# relay.net
KiCad netlist of a schematic drawn in EAGLE
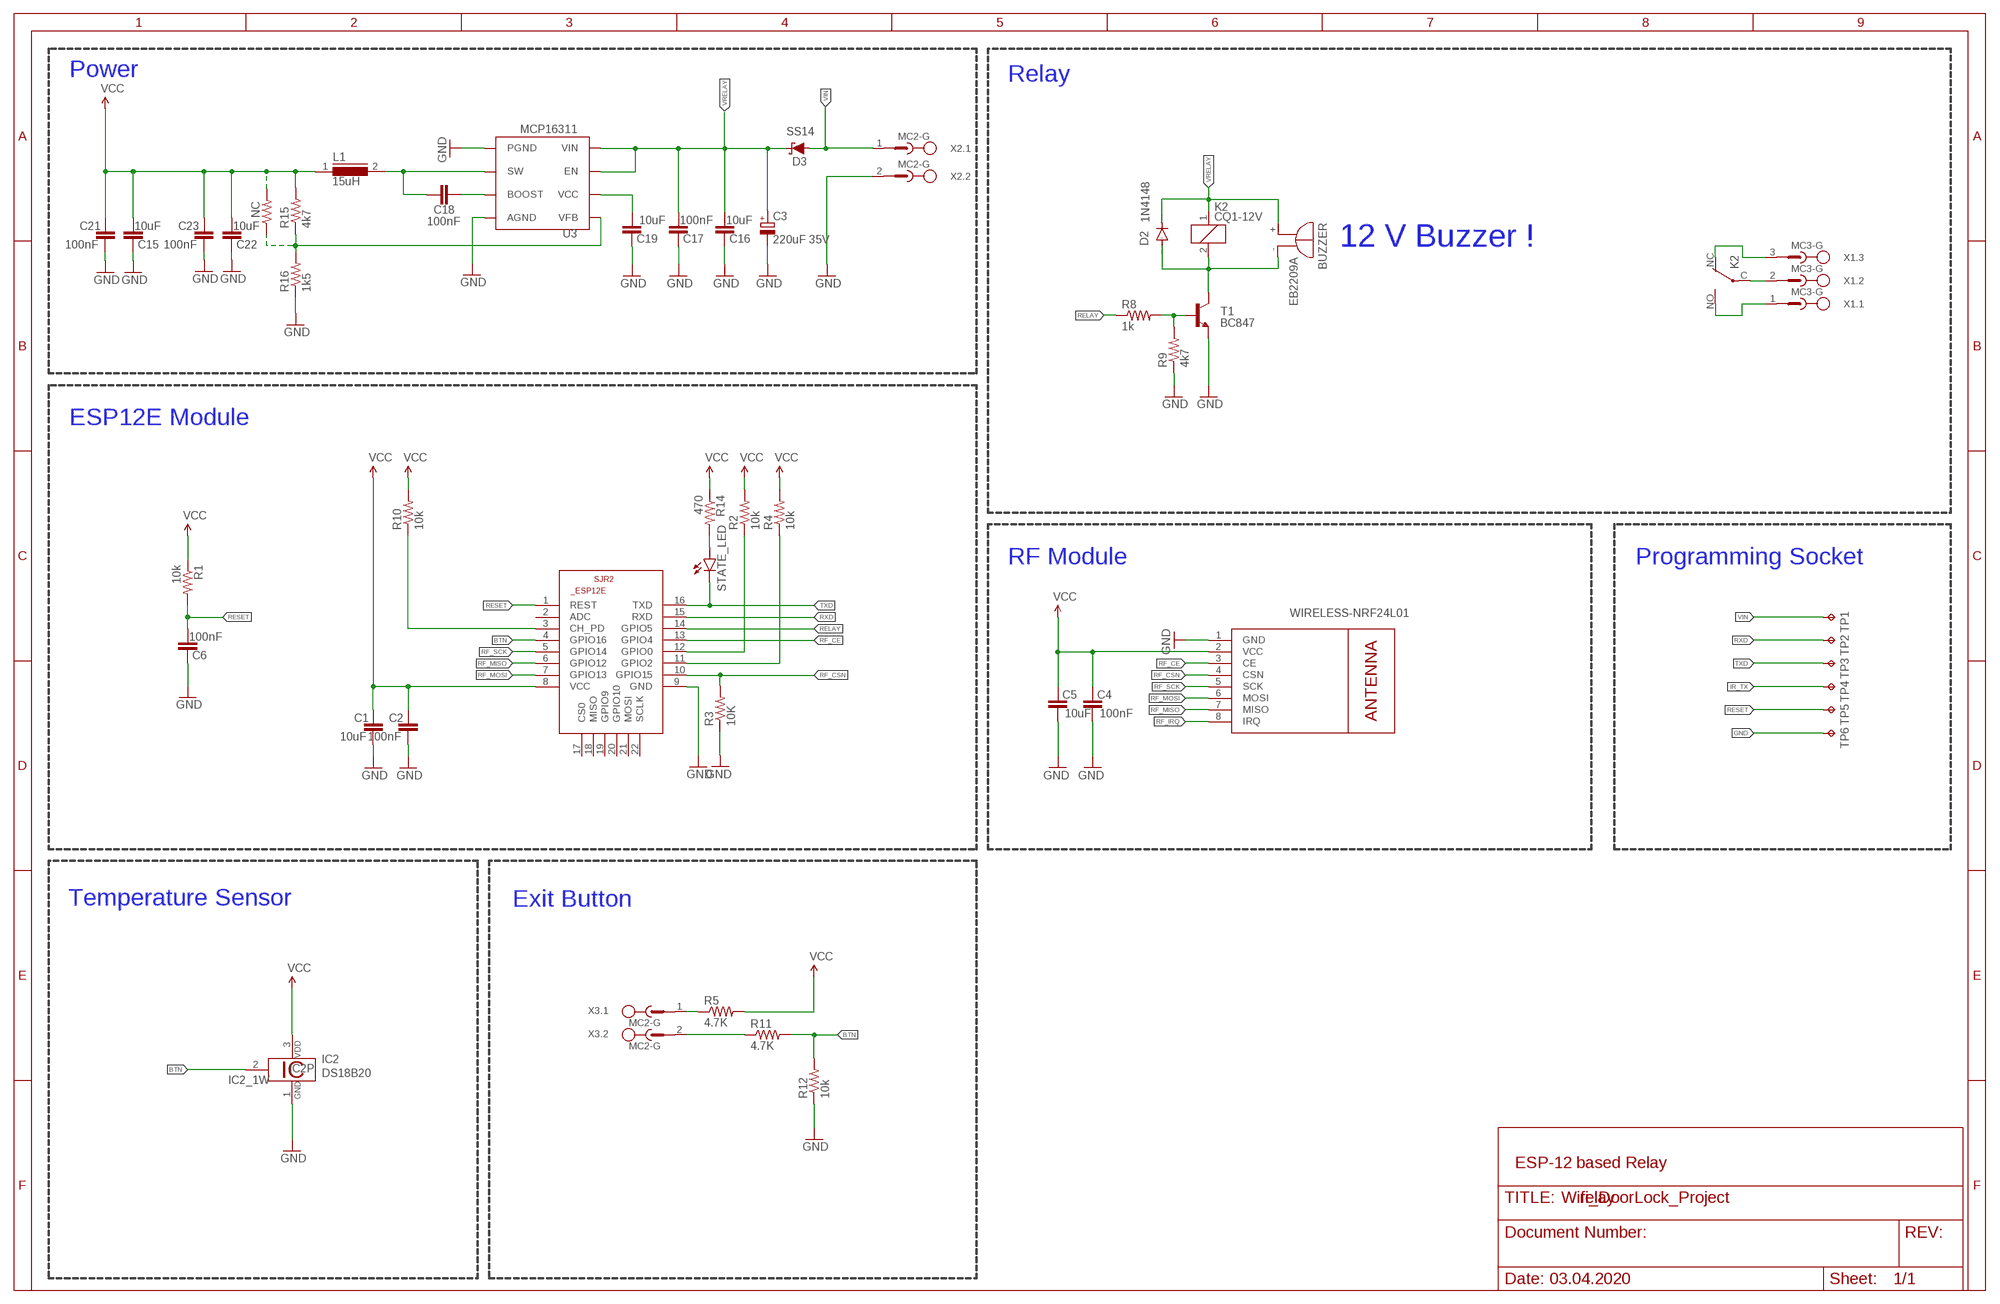
[diagram p0: schematic, sheet 1]

(export (version "E")
  (design (tool "Eeschema 10.0.6"))
  (components
    (comp (ref "BUZZER")
      (value "EB2209A")
      (footprint "eagle-import:EB2209A")
      (libsource (lib "eagle-import") (part "EB2209A"))
    )
    (comp (ref "C1")
      (value "10uF")
      (footprint "eagle-import:C0805")
      (libsource (lib "eagle-import") (part "C-EUC0805"))
    )
    (comp (ref "C2")
      (value "100nF")
      (footprint "eagle-import:C0805")
      (libsource (lib "eagle-import") (part "C-EUC0805"))
    )
    (comp (ref "C3")
      (value "220uF 35V")
      (footprint "eagle-import:150CLZ-0810")
      (libsource (lib "eagle-import") (part "CPOL-EU150CLZ-0810"))
    )
    (comp (ref "C4")
      (value "100nF")
      (footprint "eagle-import:C0805")
      (libsource (lib "eagle-import") (part "C-EUC0805"))
    )
    (comp (ref "C5")
      (value "10uF")
      (footprint "eagle-import:C0805")
      (libsource (lib "eagle-import") (part "C-EUC0805"))
    )
    (comp (ref "C6")
      (value "100nF")
      (footprint "eagle-import:C0805")
      (libsource (lib "eagle-import") (part "C-EUC0805"))
    )
    (comp (ref "C15")
      (value "10uF")
      (footprint "eagle-import:C0805")
      (libsource (lib "eagle-import") (part "C-EUC0805"))
    )
    (comp (ref "C16")
      (value "10uF")
      (footprint "eagle-import:C0805")
      (libsource (lib "eagle-import") (part "C-EUC0805"))
    )
    (comp (ref "C17")
      (value "100nF")
      (footprint "eagle-import:C0805")
      (libsource (lib "eagle-import") (part "C-EUC0805"))
    )
    (comp (ref "C18")
      (value "100nF")
      (footprint "eagle-import:C0805")
      (libsource (lib "eagle-import") (part "C-EUC0805"))
    )
    (comp (ref "C19")
      (value "10uF")
      (footprint "eagle-import:C0805")
      (libsource (lib "eagle-import") (part "C-EUC0805"))
    )
    (comp (ref "C21")
      (value "100nF")
      (footprint "eagle-import:C0805")
      (libsource (lib "eagle-import") (part "C-EUC0805"))
    )
    (comp (ref "C22")
      (value "10uF")
      (footprint "eagle-import:C0805")
      (libsource (lib "eagle-import") (part "C-EUC0805"))
    )
    (comp (ref "C23")
      (value "100nF")
      (footprint "eagle-import:C0805")
      (libsource (lib "eagle-import") (part "C-EUC0805"))
    )
    (comp (ref "D2")
      (value "1N4148")
      (footprint "eagle-import:DO-214AC")
      (libsource (lib "eagle-import") (part "DIODE-DO-214AC"))
    )
    (comp (ref "D3")
      (value "SS14")
      (footprint "eagle-import:SMA-DIODE")
      (libsource (lib "eagle-import") (part "DIODE-SCHOTTKY-SS14"))
    )
    (comp (ref "IC2")
      (value "DS18B20")
      (footprint "eagle-import:TO92-")
      (libsource (lib "eagle-import") (part "DS18B20"))
    )
    (comp (ref "K2")
      (value "CQ1-12V")
      (footprint "eagle-import:CQ1")
      (libsource (lib "eagle-import") (part "CQ1-12V"))
    )
    (comp (ref "L1")
      (value "15uH")
      (footprint "eagle-import:DR74")
      (libsource (lib "eagle-import") (part "DR74"))
    )
    (comp (ref "M1")
      (value "WIRELESS-NRF24L01")
      (footprint "eagle-import:WIRELESS-NRF24L01")
      (libsource (lib "eagle-import") (part "WIRELESS-NRF24L01"))
    )
    (comp (ref "NC")
      (value "R-US_M0805")
      (footprint "eagle-import:M0805")
      (libsource (lib "eagle-import") (part "R-US_M0805"))
    )
    (comp (ref "R1")
      (value "10k")
      (footprint "eagle-import:M0805")
      (libsource (lib "eagle-import") (part "R-US_M0805"))
    )
    (comp (ref "R2")
      (value "10k")
      (footprint "eagle-import:M0805")
      (libsource (lib "eagle-import") (part "R-US_M0805"))
    )
    (comp (ref "R3")
      (value "10K")
      (footprint "eagle-import:M0805")
      (libsource (lib "eagle-import") (part "R-US_M0805"))
    )
    (comp (ref "R4")
      (value "10k")
      (footprint "eagle-import:M0805")
      (libsource (lib "eagle-import") (part "R-US_M0805"))
    )
    (comp (ref "R5")
      (value "4.7K")
      (footprint "eagle-import:M0805")
      (libsource (lib "eagle-import") (part "R-US_M0805"))
    )
    (comp (ref "R8")
      (value "1k")
      (footprint "eagle-import:M0805")
      (libsource (lib "eagle-import") (part "R-US_M0805"))
    )
    (comp (ref "R9")
      (value "4k7")
      (footprint "eagle-import:M0805")
      (libsource (lib "eagle-import") (part "R-US_M0805"))
    )
    (comp (ref "R10")
      (value "10k")
      (footprint "eagle-import:M0805")
      (libsource (lib "eagle-import") (part "R-US_M0805"))
    )
    (comp (ref "R11")
      (value "4.7K")
      (footprint "eagle-import:M0805")
      (libsource (lib "eagle-import") (part "R-US_M0805"))
    )
    (comp (ref "R12")
      (value "10k")
      (footprint "eagle-import:M0805")
      (libsource (lib "eagle-import") (part "R-US_M0805"))
    )
    (comp (ref "R14")
      (value "470")
      (footprint "eagle-import:M0805")
      (libsource (lib "eagle-import") (part "R-US_M0805"))
    )
    (comp (ref "R15")
      (value "4k7")
      (footprint "eagle-import:M0805")
      (libsource (lib "eagle-import") (part "R-US_M0805"))
    )
    (comp (ref "R16")
      (value "1k5")
      (footprint "eagle-import:M0805")
      (libsource (lib "eagle-import") (part "R-US_M0805"))
    )
    (comp (ref "SJR2")
      (value "ESP8266-12EESP12E")
      (footprint "eagle-import:ESP8266-ESP12E")
      (libsource (lib "eagle-import") (part "ESP8266-12EESP12E"))
    )
    (comp (ref "STATE_LED")
      (value "LED3MM")
      (footprint "eagle-import:LED3MM")
      (libsource (lib "eagle-import") (part "LED3MM"))
    )
    (comp (ref "T1")
      (value "BC847")
      (footprint "eagle-import:SOT23")
      (libsource (lib "eagle-import") (part "BC847"))
    )
    (comp (ref "TP1")
      (value "TPTP20SQ")
      (footprint "eagle-import:TP20SQ")
      (libsource (lib "eagle-import") (part "TPTP20SQ"))
    )
    (comp (ref "TP2")
      (value "TPTP20SQ")
      (footprint "eagle-import:TP20SQ")
      (libsource (lib "eagle-import") (part "TPTP20SQ"))
    )
    (comp (ref "TP3")
      (value "TPTP20SQ")
      (footprint "eagle-import:TP20SQ")
      (libsource (lib "eagle-import") (part "TPTP20SQ"))
    )
    (comp (ref "TP4")
      (value "TPTP20SQ")
      (footprint "eagle-import:TP20SQ")
      (libsource (lib "eagle-import") (part "TPTP20SQ"))
    )
    (comp (ref "TP5")
      (value "TPTP20SQ")
      (footprint "eagle-import:TP20SQ")
      (libsource (lib "eagle-import") (part "TPTP20SQ"))
    )
    (comp (ref "TP6")
      (value "TPTP20SQ")
      (footprint "eagle-import:TP20SQ")
      (libsource (lib "eagle-import") (part "TPTP20SQ"))
    )
    (comp (ref "U3")
      (value "MCP16311")
      (footprint "eagle-import:MSOP8")
      (libsource (lib "eagle-import") (part "MCP16311"))
    )
    (comp (ref "X1")
      (value "MC3-G")
      (footprint "eagle-import:MC3-G")
      (libsource (lib "eagle-import") (part "MC3-G"))
    )
    (comp (ref "X2")
      (value "MC2-G")
      (footprint "eagle-import:MC2-G")
      (libsource (lib "eagle-import") (part "MC2-G"))
    )
    (comp (ref "X3")
      (value "MC2-G")
      (footprint "eagle-import:MC2-G")
      (libsource (lib "eagle-import") (part "MC2-G"))
    )
  )
  (nets
    (net (code "1") (name "BTN") (class "Default")
      (node (ref "IC2") (pin "2") (pinfunction "1W_2") (pintype "power_in"))
      (node (ref "R11") (pin "2") (pinfunction "2_2") (pintype "passive"))
      (node (ref "R12") (pin "2") (pinfunction "2_2") (pintype "passive"))
      (node (ref "SJR2") (pin "4") (pinfunction "GPIO16_4") (pintype "bidirectional"))
    )
    (net (code "2") (name "GND") (class "Default")
      (node (ref "C1") (pin "2") (pinfunction "2_2") (pintype "passive"))
      (node (ref "C15") (pin "1") (pinfunction "1_1") (pintype "passive"))
      (node (ref "C16") (pin "1") (pinfunction "1_1") (pintype "passive"))
      (node (ref "C17") (pin "1") (pinfunction "1_1") (pintype "passive"))
      (node (ref "C19") (pin "1") (pinfunction "1_1") (pintype "passive"))
      (node (ref "C2") (pin "2") (pinfunction "2_2") (pintype "passive"))
      (node (ref "C21") (pin "2") (pinfunction "2_2") (pintype "passive"))
      (node (ref "C22") (pin "1") (pinfunction "1_1") (pintype "passive"))
      (node (ref "C23") (pin "2") (pinfunction "2_2") (pintype "passive"))
      (node (ref "C3") (pin "-") (pinfunction "-_-") (pintype "passive"))
      (node (ref "C4") (pin "2") (pinfunction "2_2") (pintype "passive"))
      (node (ref "C5") (pin "2") (pinfunction "2_2") (pintype "passive"))
      (node (ref "C6") (pin "1") (pinfunction "1_1") (pintype "passive"))
      (node (ref "IC2") (pin "1") (pinfunction "GND_1") (pintype "power_in"))
      (node (ref "M1") (pin "1") (pinfunction "GND_1") (pintype "power_in"))
      (node (ref "R12") (pin "1") (pinfunction "1_1") (pintype "passive"))
      (node (ref "R16") (pin "1") (pinfunction "1_1") (pintype "passive"))
      (node (ref "R3") (pin "1") (pinfunction "1_1") (pintype "passive"))
      (node (ref "R9") (pin "1") (pinfunction "1_1") (pintype "passive"))
      (node (ref "SJR2") (pin "9") (pinfunction "GND_9") (pintype "bidirectional"))
      (node (ref "T1") (pin "2") (pinfunction "E_2") (pintype "passive"))
      (node (ref "TP6") (pin "TP") (pinfunction "TP_TP") (pintype "input"))
      (node (ref "U3") (pin "AGND") (pinfunction "AGND_AGND") (pintype "bidirectional"))
      (node (ref "U3") (pin "PGND") (pinfunction "PGND_PGND") (pintype "bidirectional"))
      (node (ref "X2") (pin "2") (pinfunction "SK_2") (pintype "passive"))
    )
    (net (code "3") (name "IR_TX") (class "Default")
      (node (ref "TP4") (pin "TP") (pinfunction "TP_TP") (pintype "input"))
    )
    (net (code "4") (name "Net-(C18-Pad1)") (class "Default")
      (node (ref "C18") (pin "1") (pinfunction "1_1") (pintype "passive"))
      (node (ref "U3") (pin "BOOST") (pinfunction "BOOST_BOOST") (pintype "bidirectional"))
    )
    (net (code "5") (name "Net-(C18-Pad2)") (class "Default")
      (node (ref "C18") (pin "2") (pinfunction "2_2") (pintype "passive"))
      (node (ref "L1") (pin "2") (pinfunction "2_2") (pintype "passive"))
      (node (ref "U3") (pin "SW") (pinfunction "SW_SW") (pintype "bidirectional"))
    )
    (net (code "6") (name "Net-(C19-Pad2)") (class "Default")
      (node (ref "C19") (pin "2") (pinfunction "2_2") (pintype "passive"))
      (node (ref "U3") (pin "VCC") (pinfunction "VCC_VCC") (pintype "bidirectional"))
    )
    (net (code "7") (name "Net-(K2B-O)") (class "Default")
      (node (ref "K2") (pin "NC") (pinfunction "O_NC") (pintype "passive"))
      (node (ref "X1") (pin "3") (pinfunction "SK_3") (pintype "passive"))
    )
    (net (code "8") (name "Net-(K2B-P)") (class "Default")
      (node (ref "K2") (pin "C") (pinfunction "P_C") (pintype "passive"))
      (node (ref "X1") (pin "2") (pinfunction "SK_2") (pintype "passive"))
    )
    (net (code "9") (name "Net-(K2B-S)") (class "Default")
      (node (ref "K2") (pin "NO") (pinfunction "S_NO") (pintype "passive"))
      (node (ref "X1") (pin "1") (pinfunction "SK_1") (pintype "passive"))
    )
    (net (code "10") (name "Net-(NC-Pad1)") (class "Default")
      (node (ref "NC") (pin "1") (pinfunction "1_1") (pintype "passive"))
      (node (ref "R15") (pin "1") (pinfunction "1_1") (pintype "passive"))
      (node (ref "R16") (pin "2") (pinfunction "2_2") (pintype "passive"))
      (node (ref "U3") (pin "VFB") (pinfunction "VFB_VFB") (pintype "bidirectional"))
    )
    (net (code "11") (name "Net-(R14-Pad2)") (class "Default")
      (node (ref "R14") (pin "2") (pinfunction "2_2") (pintype "passive"))
      (node (ref "STATE_LED") (pin "A") (pinfunction "A_A") (pintype "passive"))
    )
    (net (code "12") (name "Net-(SJR2-CH_PD)") (class "Default")
      (node (ref "R10") (pin "1") (pinfunction "1_1") (pintype "passive"))
      (node (ref "SJR2") (pin "3") (pinfunction "CH_PD_3") (pintype "bidirectional"))
    )
    (net (code "13") (name "Net-(SJR2-GPIO0)") (class "Default")
      (node (ref "R2") (pin "1") (pinfunction "1_1") (pintype "passive"))
      (node (ref "SJR2") (pin "12") (pinfunction "GPIO0_12") (pintype "bidirectional"))
    )
    (net (code "14") (name "Net-(SJR2-GPIO2)") (class "Default")
      (node (ref "R4") (pin "1") (pinfunction "1_1") (pintype "passive"))
      (node (ref "SJR2") (pin "11") (pinfunction "GPIO2_11") (pintype "bidirectional"))
    )
    (net (code "15") (name "Net-(T1-B)") (class "Default")
      (node (ref "R8") (pin "2") (pinfunction "2_2") (pintype "passive"))
      (node (ref "R9") (pin "2") (pinfunction "2_2") (pintype "passive"))
      (node (ref "T1") (pin "1") (pinfunction "B_1") (pintype "passive"))
    )
    (net (code "16") (name "Net-(T1-C)") (class "Default")
      (node (ref "BUZZER") (pin "-") (pinfunction "-_-") (pintype "passive"))
      (node (ref "D2") (pin "A") (pinfunction "A_A") (pintype "passive"))
      (node (ref "K2") (pin "2") (pinfunction "2_2") (pintype "passive"))
      (node (ref "T1") (pin "3") (pinfunction "C_3") (pintype "passive"))
    )
    (net (code "17") (name "Net-(X3A-SK)") (class "Default")
      (node (ref "R5") (pin "1") (pinfunction "1_1") (pintype "passive"))
      (node (ref "X3") (pin "1") (pinfunction "SK_1") (pintype "passive"))
    )
    (net (code "18") (name "Net-(X3B-SK)") (class "Default")
      (node (ref "R11") (pin "1") (pinfunction "1_1") (pintype "passive"))
      (node (ref "X3") (pin "2") (pinfunction "SK_2") (pintype "passive"))
    )
    (net (code "19") (name "RELAY") (class "Default")
      (node (ref "R8") (pin "1") (pinfunction "1_1") (pintype "passive"))
      (node (ref "SJR2") (pin "14") (pinfunction "GPIO5_14") (pintype "bidirectional"))
    )
    (net (code "20") (name "RESET") (class "Default")
      (node (ref "C6") (pin "2") (pinfunction "2_2") (pintype "passive"))
      (node (ref "R1") (pin "2") (pinfunction "2_2") (pintype "passive"))
      (node (ref "SJR2") (pin "1") (pinfunction "REST_1") (pintype "bidirectional"))
      (node (ref "TP5") (pin "TP") (pinfunction "TP_TP") (pintype "input"))
    )
    (net (code "21") (name "RF_CE") (class "Default")
      (node (ref "M1") (pin "3") (pinfunction "CE_3") (pintype "bidirectional"))
      (node (ref "SJR2") (pin "13") (pinfunction "GPIO4_13") (pintype "bidirectional"))
    )
    (net (code "22") (name "RF_CSN") (class "Default")
      (node (ref "M1") (pin "4") (pinfunction "CSN_4") (pintype "bidirectional"))
      (node (ref "R3") (pin "2") (pinfunction "2_2") (pintype "passive"))
      (node (ref "SJR2") (pin "10") (pinfunction "GPIO15_10") (pintype "bidirectional"))
    )
    (net (code "23") (name "RF_IRQ") (class "Default")
      (node (ref "M1") (pin "8") (pinfunction "IRQ_8") (pintype "bidirectional"))
    )
    (net (code "24") (name "RF_MISO") (class "Default")
      (node (ref "M1") (pin "7") (pinfunction "MISO_7") (pintype "bidirectional"))
      (node (ref "SJR2") (pin "6") (pinfunction "GPIO12_6") (pintype "bidirectional"))
    )
    (net (code "25") (name "RF_MOSI") (class "Default")
      (node (ref "M1") (pin "6") (pinfunction "MOSI_6") (pintype "bidirectional"))
      (node (ref "SJR2") (pin "7") (pinfunction "GPIO13_7") (pintype "bidirectional"))
    )
    (net (code "26") (name "RF_SCK") (class "Default")
      (node (ref "M1") (pin "5") (pinfunction "SCK_5") (pintype "bidirectional"))
      (node (ref "SJR2") (pin "5") (pinfunction "GPIO14_5") (pintype "bidirectional"))
    )
    (net (code "27") (name "RXD") (class "Default")
      (node (ref "SJR2") (pin "15") (pinfunction "RXD_15") (pintype "bidirectional"))
      (node (ref "TP2") (pin "TP") (pinfunction "TP_TP") (pintype "input"))
    )
    (net (code "28") (name "TXD") (class "Default")
      (node (ref "SJR2") (pin "16") (pinfunction "TXD_16") (pintype "bidirectional"))
      (node (ref "STATE_LED") (pin "K") (pinfunction "C_K") (pintype "passive"))
      (node (ref "TP3") (pin "TP") (pinfunction "TP_TP") (pintype "input"))
    )
    (net (code "29") (name "VCC") (class "Default")
      (node (ref "C1") (pin "1") (pinfunction "1_1") (pintype "passive"))
      (node (ref "C15") (pin "2") (pinfunction "2_2") (pintype "passive"))
      (node (ref "C2") (pin "1") (pinfunction "1_1") (pintype "passive"))
      (node (ref "C21") (pin "1") (pinfunction "1_1") (pintype "passive"))
      (node (ref "C22") (pin "2") (pinfunction "2_2") (pintype "passive"))
      (node (ref "C23") (pin "1") (pinfunction "1_1") (pintype "passive"))
      (node (ref "C4") (pin "1") (pinfunction "1_1") (pintype "passive"))
      (node (ref "C5") (pin "1") (pinfunction "1_1") (pintype "passive"))
      (node (ref "IC2") (pin "3") (pinfunction "VDD_3") (pintype "power_in"))
      (node (ref "L1") (pin "1") (pinfunction "1_1") (pintype "passive"))
      (node (ref "M1") (pin "2") (pinfunction "VCC_2") (pintype "power_in"))
      (node (ref "NC") (pin "2") (pinfunction "2_2") (pintype "passive"))
      (node (ref "R1") (pin "1") (pinfunction "1_1") (pintype "passive"))
      (node (ref "R10") (pin "2") (pinfunction "2_2") (pintype "passive"))
      (node (ref "R14") (pin "1") (pinfunction "1_1") (pintype "passive"))
      (node (ref "R15") (pin "2") (pinfunction "2_2") (pintype "passive"))
      (node (ref "R2") (pin "2") (pinfunction "2_2") (pintype "passive"))
      (node (ref "R4") (pin "2") (pinfunction "2_2") (pintype "passive"))
      (node (ref "R5") (pin "2") (pinfunction "2_2") (pintype "passive"))
      (node (ref "SJR2") (pin "8") (pinfunction "VCC_8") (pintype "bidirectional"))
    )
    (net (code "30") (name "VIN") (class "Default")
      (node (ref "D3") (pin "A") (pinfunction "A_A") (pintype "passive"))
      (node (ref "TP1") (pin "TP") (pinfunction "TP_TP") (pintype "input"))
      (node (ref "X2") (pin "1") (pinfunction "SK_1") (pintype "passive"))
    )
    (net (code "31") (name "VRELAY") (class "Default")
      (node (ref "BUZZER") (pin "+") (pinfunction "+_+") (pintype "passive"))
      (node (ref "C16") (pin "2") (pinfunction "2_2") (pintype "passive"))
      (node (ref "C17") (pin "2") (pinfunction "2_2") (pintype "passive"))
      (node (ref "C3") (pin "+") (pinfunction "+_+") (pintype "passive"))
      (node (ref "D2") (pin "C") (pinfunction "C_C") (pintype "passive"))
      (node (ref "D3") (pin "C") (pinfunction "C_C") (pintype "passive"))
      (node (ref "K2") (pin "1") (pinfunction "1_1") (pintype "passive"))
      (node (ref "U3") (pin "EN") (pinfunction "EN_EN") (pintype "bidirectional"))
      (node (ref "U3") (pin "VIN") (pinfunction "VIN_VIN") (pintype "bidirectional"))
    )
    (net (code "32") (name "unconnected-(SJR2-ADC-Pad2)") (class "Default")
      (node (ref "SJR2") (pin "2") (pinfunction "ADC_2") (pintype "bidirectional"))
    )
    (net (code "33") (name "unconnected-(SJR2-CS0-Pad17)") (class "Default")
      (node (ref "SJR2") (pin "17") (pinfunction "CS0_17") (pintype "bidirectional"))
    )
    (net (code "34") (name "unconnected-(SJR2-GPIO9-Pad19)") (class "Default")
      (node (ref "SJR2") (pin "19") (pinfunction "GPIO9_19") (pintype "bidirectional"))
    )
    (net (code "35") (name "unconnected-(SJR2-GPIO10-Pad20)") (class "Default")
      (node (ref "SJR2") (pin "20") (pinfunction "GPIO10_20") (pintype "bidirectional"))
    )
    (net (code "36") (name "unconnected-(SJR2-MISO-Pad18)") (class "Default")
      (node (ref "SJR2") (pin "18") (pinfunction "MISO_18") (pintype "bidirectional"))
    )
    (net (code "37") (name "unconnected-(SJR2-MOSI-Pad21)") (class "Default")
      (node (ref "SJR2") (pin "21") (pinfunction "MOSI_21") (pintype "bidirectional"))
    )
    (net (code "38") (name "unconnected-(SJR2-SCLK-Pad22)") (class "Default")
      (node (ref "SJR2") (pin "22") (pinfunction "SCLK_22") (pintype "bidirectional"))
    )
  )
)
